# Sheet1.net
KiCad netlist of a schematic drawn in Altium Designer
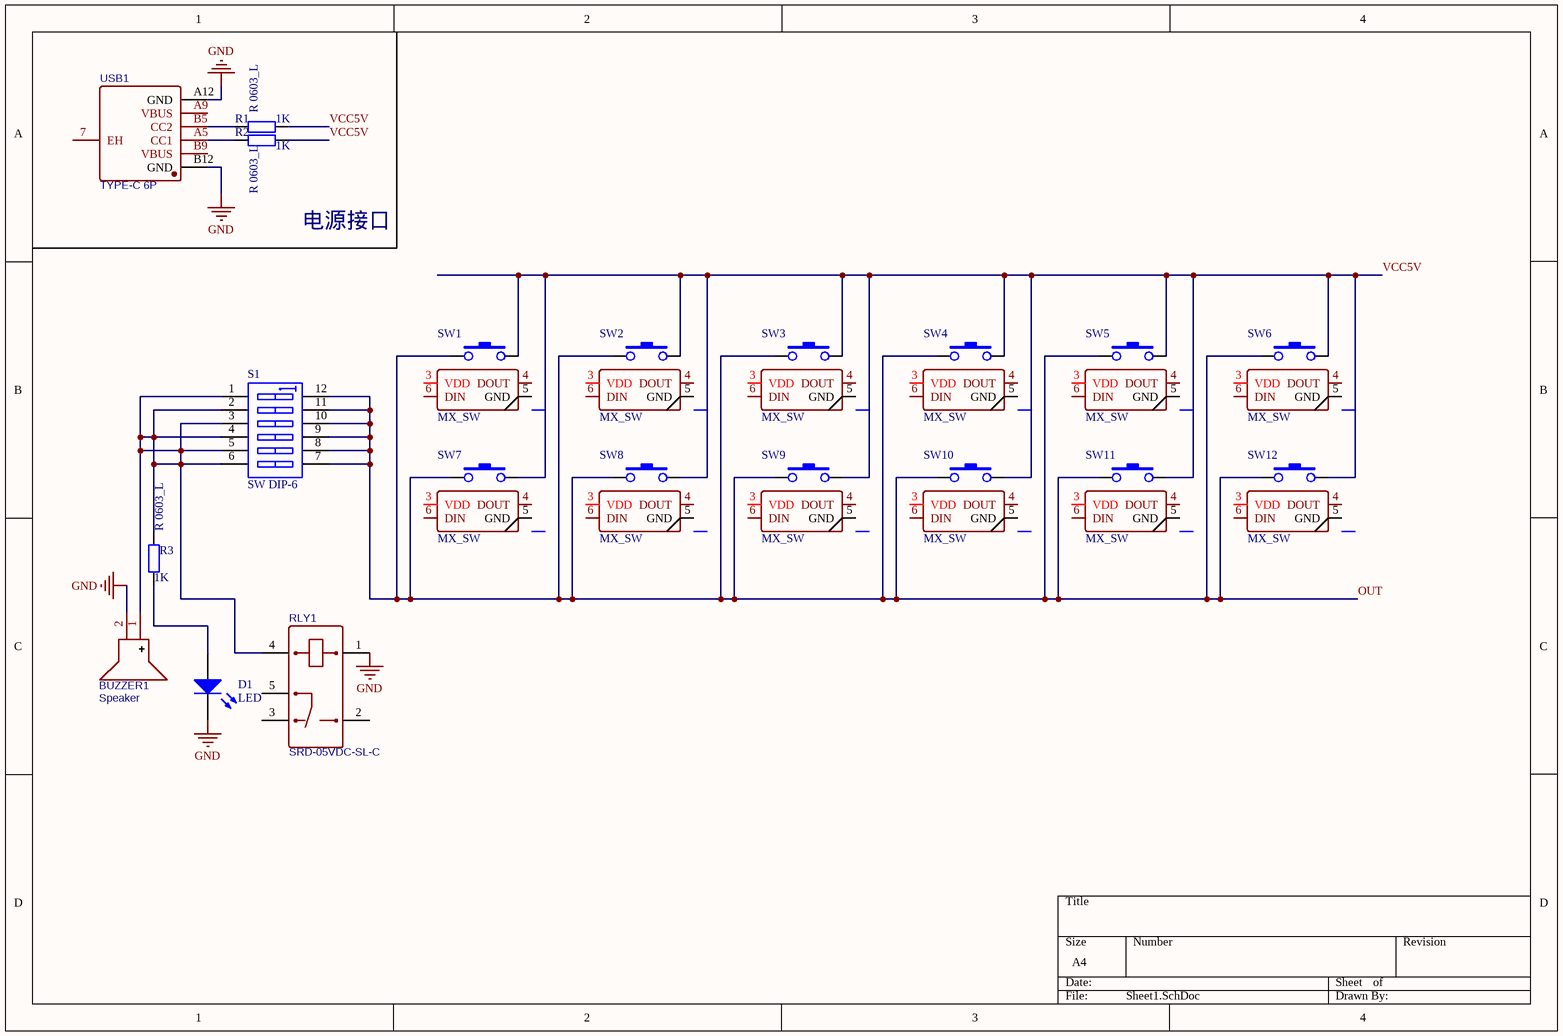
[diagram p0: Sheet1.SchDoc]

(export (version "E")
  (design (tool "Eeschema 10.0.6"))
  (components
    (comp (ref "BUZZER1")
      (value "Speaker")
      (footprint "Speaker")
      (fields
        (field (name "BOM_SUPPLIER PART") "C482357")
        (field (name "BOM_MANUFACTURER PART") "FMB1275-05")
        (field (name "CONTRIBUTOR") "LCSC")
      )
      (libsource (lib "Schlib1") (part "Speaker"))
    )
    (comp (ref "D1")
      (value "LED")
      (footprint "LED 0805R")
      (description "Typical INFRARED GaAs LED")
      (fields (field (name "PUBLISHER") "Altium Limited"))
      (libsource (lib "Schlib1") (part "LED 0805R 红"))
    )
    (comp (ref "R1")
      (value "R 0603_L")
      (footprint "R 0603_L")
      (description "Resistor")
      (fields (field (name "ALTIUM_VALUE") "1K") (field (name "PUBLISHER") "Altium Limited"))
      (libsource (lib "Schlib1") (part "R 0603_L"))
    )
    (comp (ref "R2")
      (value "R 0603_L")
      (footprint "R 0603_L")
      (description "Resistor")
      (fields (field (name "ALTIUM_VALUE") "1K") (field (name "PUBLISHER") "Altium Limited"))
      (libsource (lib "Schlib1") (part "R 0603_L"))
    )
    (comp (ref "R3")
      (value "R 0603_L")
      (footprint "R 0603_L")
      (description "Resistor")
      (fields (field (name "ALTIUM_VALUE") "1K") (field (name "PUBLISHER") "Altium Limited"))
      (libsource (lib "") (part "R 0603_L_1"))
    )
    (comp (ref "RLY1")
      (value "SRD-05VDC-SL-C")
      (footprint "SRD-05VDC-SL-C")
      (fields (field (name "BOM_SUPPLIER PART") "C35449"))
      (libsource (lib "Schlib1") (part "SRD-05VDC-SL-C"))
    )
    (comp (ref "S1")
      (value "SW DIP-6")
      (footprint "DIP-12/SW")
      (description "DIP Switch, 6 Position, SPST")
      (fields (field (name "PUBLISHER") "Altium Limited"))
      (libsource (lib "Miscellaneous Devices") (part "SW DIP-6"))
    )
    (comp (ref "SW1") (value "MX_SW") (footprint "MX_SW-1") (libsource (lib "Schlib1") (part "MX_SW-1")))
    (comp (ref "SW2") (value "MX_SW") (footprint "MX_SW-1") (libsource (lib "Schlib1") (part "MX_SW-1")))
    (comp (ref "SW3") (value "MX_SW") (footprint "MX_SW-1") (libsource (lib "Schlib1") (part "MX_SW-1")))
    (comp (ref "SW4") (value "MX_SW") (footprint "MX_SW-1") (libsource (lib "Schlib1") (part "MX_SW-1")))
    (comp (ref "SW5") (value "MX_SW") (footprint "MX_SW-1") (libsource (lib "Schlib1") (part "MX_SW-1")))
    (comp (ref "SW6") (value "MX_SW") (footprint "MX_SW-1") (libsource (lib "Schlib1") (part "MX_SW-1")))
    (comp (ref "SW7") (value "MX_SW") (footprint "MX_SW-1") (libsource (lib "Schlib1") (part "MX_SW-1")))
    (comp (ref "SW8") (value "MX_SW") (footprint "MX_SW-1") (libsource (lib "Schlib1") (part "MX_SW-1")))
    (comp (ref "SW9") (value "MX_SW") (footprint "MX_SW-1") (libsource (lib "Schlib1") (part "MX_SW-1")))
    (comp (ref "SW10") (value "MX_SW") (footprint "MX_SW-1") (libsource (lib "Schlib1") (part "MX_SW-1")))
    (comp (ref "SW11") (value "MX_SW") (footprint "MX_SW-1") (libsource (lib "Schlib1") (part "MX_SW-1")))
    (comp (ref "SW12") (value "MX_SW") (footprint "MX_SW-1") (libsource (lib "Schlib1") (part "MX_SW-1")))
    (comp (ref "USB1")
      (value "TYPE-C 6P")
      (footprint "TYPE-C-SMD_TYPE-C-6P")
      (fields (field (name "BOM_SUPPLIER PART") "C456012") (field (name "CONTRIBUTOR") "LCSC"))
      (libsource (lib "Schlib1") (part "TYPE-C 6P"))
    )
  )
  (nets
    (net (code "1") (name "/OUT") (class "Default")
      (node (ref "S1") (pin "10") (pinfunction "B3_10") (pintype "passive"))
      (node (ref "S1") (pin "11") (pinfunction "B2_11") (pintype "passive"))
      (node (ref "S1") (pin "12") (pinfunction "B1_12") (pintype "passive"))
      (node (ref "S1") (pin "7") (pinfunction "B6_7") (pintype "passive"))
      (node (ref "S1") (pin "8") (pinfunction "B5_8") (pintype "passive"))
      (node (ref "S1") (pin "9") (pinfunction "B4_9") (pintype "passive"))
      (node (ref "SW1") (pin "1") (pinfunction "1_1") (pintype "passive"))
      (node (ref "SW10") (pin "1") (pinfunction "1_1") (pintype "passive"))
      (node (ref "SW11") (pin "1") (pinfunction "1_1") (pintype "passive"))
      (node (ref "SW12") (pin "1") (pinfunction "1_1") (pintype "passive"))
      (node (ref "SW2") (pin "1") (pinfunction "1_1") (pintype "passive"))
      (node (ref "SW3") (pin "1") (pinfunction "1_1") (pintype "passive"))
      (node (ref "SW4") (pin "1") (pinfunction "1_1") (pintype "passive"))
      (node (ref "SW5") (pin "1") (pinfunction "1_1") (pintype "passive"))
      (node (ref "SW6") (pin "1") (pinfunction "1_1") (pintype "passive"))
      (node (ref "SW7") (pin "1") (pinfunction "1_1") (pintype "passive"))
      (node (ref "SW8") (pin "1") (pinfunction "1_1") (pintype "passive"))
      (node (ref "SW9") (pin "1") (pinfunction "1_1") (pintype "passive"))
    )
    (net (code "2") (name "/VCC5V") (class "Default")
      (node (ref "R1") (pin "2") (pinfunction "2_2") (pintype "passive"))
      (node (ref "R2") (pin "2") (pinfunction "2_2") (pintype "passive"))
      (node (ref "SW1") (pin "2") (pinfunction "2_2") (pintype "passive"))
      (node (ref "SW10") (pin "2") (pinfunction "2_2") (pintype "passive"))
      (node (ref "SW11") (pin "2") (pinfunction "2_2") (pintype "passive"))
      (node (ref "SW12") (pin "2") (pinfunction "2_2") (pintype "passive"))
      (node (ref "SW2") (pin "2") (pinfunction "2_2") (pintype "passive"))
      (node (ref "SW3") (pin "2") (pinfunction "2_2") (pintype "passive"))
      (node (ref "SW4") (pin "2") (pinfunction "2_2") (pintype "passive"))
      (node (ref "SW5") (pin "2") (pinfunction "2_2") (pintype "passive"))
      (node (ref "SW6") (pin "2") (pinfunction "2_2") (pintype "passive"))
      (node (ref "SW7") (pin "2") (pinfunction "2_2") (pintype "passive"))
      (node (ref "SW8") (pin "2") (pinfunction "2_2") (pintype "passive"))
      (node (ref "SW9") (pin "2") (pinfunction "2_2") (pintype "passive"))
    )
    (net (code "3") (name "GND") (class "Default")
      (node (ref "BUZZER1") (pin "2") (pinfunction "-_2") (pintype "passive"))
      (node (ref "D1") (pin "2") (pinfunction "K_2") (pintype "passive"))
      (node (ref "RLY1") (pin "1") (pinfunction "1_1") (pintype "passive"))
      (node (ref "USB1") (pin "A12") (pinfunction "GND_A12") (pintype "passive"))
      (node (ref "USB1") (pin "B12") (pinfunction "GND_B12") (pintype "passive"))
    )
    (net (code "4") (name "Net-(BUZZER1-+)") (class "Default")
      (node (ref "BUZZER1") (pin "1") (pinfunction "+_1") (pintype "passive"))
      (node (ref "R3") (pin "1") (pinfunction "1_1") (pintype "passive"))
      (node (ref "RLY1") (pin "4") (pinfunction "4_4") (pintype "passive"))
      (node (ref "S1") (pin "1") (pinfunction "A1_1") (pintype "passive"))
      (node (ref "S1") (pin "2") (pinfunction "A2_2") (pintype "passive"))
      (node (ref "S1") (pin "3") (pinfunction "A3_3") (pintype "passive"))
      (node (ref "S1") (pin "4") (pinfunction "A4_4") (pintype "passive"))
      (node (ref "S1") (pin "5") (pinfunction "A5_5") (pintype "passive"))
      (node (ref "S1") (pin "6") (pinfunction "A6_6") (pintype "passive"))
    )
    (net (code "5") (name "Net-(D1-A)") (class "Default")
      (node (ref "D1") (pin "1") (pinfunction "A_1") (pintype "passive"))
      (node (ref "R3") (pin "2") (pinfunction "2_2") (pintype "passive"))
    )
    (net (code "6") (name "Net-(USB1-CC1)") (class "Default")
      (node (ref "R2") (pin "1") (pinfunction "1_1") (pintype "passive"))
      (node (ref "USB1") (pin "A5") (pinfunction "CC1_A5") (pintype "passive"))
    )
    (net (code "7") (name "Net-(USB1-CC2)") (class "Default")
      (node (ref "R1") (pin "1") (pinfunction "1_1") (pintype "passive"))
      (node (ref "USB1") (pin "B5") (pinfunction "CC2_B5") (pintype "passive"))
    )
    (net (code "8") (name "unconnected-(RLY1-Pad2)") (class "Default")
      (node (ref "RLY1") (pin "2") (pinfunction "2_2") (pintype "passive"))
    )
    (net (code "9") (name "unconnected-(RLY1-Pad3)") (class "Default")
      (node (ref "RLY1") (pin "3") (pinfunction "3_3") (pintype "passive"))
    )
    (net (code "10") (name "unconnected-(RLY1-Pad5)") (class "Default")
      (node (ref "RLY1") (pin "5") (pinfunction "5_5") (pintype "passive"))
    )
    (net (code "11") (name "unconnected-(SW1-DIN-Pad6)") (class "Default")
      (node (ref "SW1") (pin "6") (pinfunction "DIN_6") (pintype "passive"))
    )
    (net (code "12") (name "unconnected-(SW1-DOUT-Pad4)") (class "Default")
      (node (ref "SW1") (pin "4") (pinfunction "DOUT_4") (pintype "passive"))
    )
    (net (code "13") (name "unconnected-(SW1-GND-Pad5)") (class "Default")
      (node (ref "SW1") (pin "5") (pinfunction "GND_5") (pintype "passive"))
    )
    (net (code "14") (name "unconnected-(SW1-VDD-Pad3)") (class "Default")
      (node (ref "SW1") (pin "3") (pinfunction "VDD_3") (pintype "passive"))
    )
    (net (code "15") (name "unconnected-(SW2-DIN-Pad6)") (class "Default")
      (node (ref "SW2") (pin "6") (pinfunction "DIN_6") (pintype "passive"))
    )
    (net (code "16") (name "unconnected-(SW2-DOUT-Pad4)") (class "Default")
      (node (ref "SW2") (pin "4") (pinfunction "DOUT_4") (pintype "passive"))
    )
    (net (code "17") (name "unconnected-(SW2-GND-Pad5)") (class "Default")
      (node (ref "SW2") (pin "5") (pinfunction "GND_5") (pintype "passive"))
    )
    (net (code "18") (name "unconnected-(SW2-VDD-Pad3)") (class "Default")
      (node (ref "SW2") (pin "3") (pinfunction "VDD_3") (pintype "passive"))
    )
    (net (code "19") (name "unconnected-(SW3-DIN-Pad6)") (class "Default")
      (node (ref "SW3") (pin "6") (pinfunction "DIN_6") (pintype "passive"))
    )
    (net (code "20") (name "unconnected-(SW3-DOUT-Pad4)") (class "Default")
      (node (ref "SW3") (pin "4") (pinfunction "DOUT_4") (pintype "passive"))
    )
    (net (code "21") (name "unconnected-(SW3-GND-Pad5)") (class "Default")
      (node (ref "SW3") (pin "5") (pinfunction "GND_5") (pintype "passive"))
    )
    (net (code "22") (name "unconnected-(SW3-VDD-Pad3)") (class "Default")
      (node (ref "SW3") (pin "3") (pinfunction "VDD_3") (pintype "passive"))
    )
    (net (code "23") (name "unconnected-(SW4-DIN-Pad6)") (class "Default")
      (node (ref "SW4") (pin "6") (pinfunction "DIN_6") (pintype "passive"))
    )
    (net (code "24") (name "unconnected-(SW4-DOUT-Pad4)") (class "Default")
      (node (ref "SW4") (pin "4") (pinfunction "DOUT_4") (pintype "passive"))
    )
    (net (code "25") (name "unconnected-(SW4-GND-Pad5)") (class "Default")
      (node (ref "SW4") (pin "5") (pinfunction "GND_5") (pintype "passive"))
    )
    (net (code "26") (name "unconnected-(SW4-VDD-Pad3)") (class "Default")
      (node (ref "SW4") (pin "3") (pinfunction "VDD_3") (pintype "passive"))
    )
    (net (code "27") (name "unconnected-(SW5-DIN-Pad6)") (class "Default")
      (node (ref "SW5") (pin "6") (pinfunction "DIN_6") (pintype "passive"))
    )
    (net (code "28") (name "unconnected-(SW5-DOUT-Pad4)") (class "Default")
      (node (ref "SW5") (pin "4") (pinfunction "DOUT_4") (pintype "passive"))
    )
    (net (code "29") (name "unconnected-(SW5-GND-Pad5)") (class "Default")
      (node (ref "SW5") (pin "5") (pinfunction "GND_5") (pintype "passive"))
    )
    (net (code "30") (name "unconnected-(SW5-VDD-Pad3)") (class "Default")
      (node (ref "SW5") (pin "3") (pinfunction "VDD_3") (pintype "passive"))
    )
    (net (code "31") (name "unconnected-(SW6-DIN-Pad6)") (class "Default")
      (node (ref "SW6") (pin "6") (pinfunction "DIN_6") (pintype "passive"))
    )
    (net (code "32") (name "unconnected-(SW6-DOUT-Pad4)") (class "Default")
      (node (ref "SW6") (pin "4") (pinfunction "DOUT_4") (pintype "passive"))
    )
    (net (code "33") (name "unconnected-(SW6-GND-Pad5)") (class "Default")
      (node (ref "SW6") (pin "5") (pinfunction "GND_5") (pintype "passive"))
    )
    (net (code "34") (name "unconnected-(SW6-VDD-Pad3)") (class "Default")
      (node (ref "SW6") (pin "3") (pinfunction "VDD_3") (pintype "passive"))
    )
    (net (code "35") (name "unconnected-(SW7-DIN-Pad6)") (class "Default")
      (node (ref "SW7") (pin "6") (pinfunction "DIN_6") (pintype "passive"))
    )
    (net (code "36") (name "unconnected-(SW7-DOUT-Pad4)") (class "Default")
      (node (ref "SW7") (pin "4") (pinfunction "DOUT_4") (pintype "passive"))
    )
    (net (code "37") (name "unconnected-(SW7-GND-Pad5)") (class "Default")
      (node (ref "SW7") (pin "5") (pinfunction "GND_5") (pintype "passive"))
    )
    (net (code "38") (name "unconnected-(SW7-VDD-Pad3)") (class "Default")
      (node (ref "SW7") (pin "3") (pinfunction "VDD_3") (pintype "passive"))
    )
    (net (code "39") (name "unconnected-(SW8-DIN-Pad6)") (class "Default")
      (node (ref "SW8") (pin "6") (pinfunction "DIN_6") (pintype "passive"))
    )
    (net (code "40") (name "unconnected-(SW8-DOUT-Pad4)") (class "Default")
      (node (ref "SW8") (pin "4") (pinfunction "DOUT_4") (pintype "passive"))
    )
    (net (code "41") (name "unconnected-(SW8-GND-Pad5)") (class "Default")
      (node (ref "SW8") (pin "5") (pinfunction "GND_5") (pintype "passive"))
    )
    (net (code "42") (name "unconnected-(SW8-VDD-Pad3)") (class "Default")
      (node (ref "SW8") (pin "3") (pinfunction "VDD_3") (pintype "passive"))
    )
    (net (code "43") (name "unconnected-(SW9-DIN-Pad6)") (class "Default")
      (node (ref "SW9") (pin "6") (pinfunction "DIN_6") (pintype "passive"))
    )
    (net (code "44") (name "unconnected-(SW9-DOUT-Pad4)") (class "Default")
      (node (ref "SW9") (pin "4") (pinfunction "DOUT_4") (pintype "passive"))
    )
    (net (code "45") (name "unconnected-(SW9-GND-Pad5)") (class "Default")
      (node (ref "SW9") (pin "5") (pinfunction "GND_5") (pintype "passive"))
    )
    (net (code "46") (name "unconnected-(SW9-VDD-Pad3)") (class "Default")
      (node (ref "SW9") (pin "3") (pinfunction "VDD_3") (pintype "passive"))
    )
    (net (code "47") (name "unconnected-(SW10-DIN-Pad6)") (class "Default")
      (node (ref "SW10") (pin "6") (pinfunction "DIN_6") (pintype "passive"))
    )
    (net (code "48") (name "unconnected-(SW10-DOUT-Pad4)") (class "Default")
      (node (ref "SW10") (pin "4") (pinfunction "DOUT_4") (pintype "passive"))
    )
    (net (code "49") (name "unconnected-(SW10-GND-Pad5)") (class "Default")
      (node (ref "SW10") (pin "5") (pinfunction "GND_5") (pintype "passive"))
    )
    (net (code "50") (name "unconnected-(SW10-VDD-Pad3)") (class "Default")
      (node (ref "SW10") (pin "3") (pinfunction "VDD_3") (pintype "passive"))
    )
    (net (code "51") (name "unconnected-(SW11-DIN-Pad6)") (class "Default")
      (node (ref "SW11") (pin "6") (pinfunction "DIN_6") (pintype "passive"))
    )
    (net (code "52") (name "unconnected-(SW11-DOUT-Pad4)") (class "Default")
      (node (ref "SW11") (pin "4") (pinfunction "DOUT_4") (pintype "passive"))
    )
    (net (code "53") (name "unconnected-(SW11-GND-Pad5)") (class "Default")
      (node (ref "SW11") (pin "5") (pinfunction "GND_5") (pintype "passive"))
    )
    (net (code "54") (name "unconnected-(SW11-VDD-Pad3)") (class "Default")
      (node (ref "SW11") (pin "3") (pinfunction "VDD_3") (pintype "passive"))
    )
    (net (code "55") (name "unconnected-(SW12-DIN-Pad6)") (class "Default")
      (node (ref "SW12") (pin "6") (pinfunction "DIN_6") (pintype "passive"))
    )
    (net (code "56") (name "unconnected-(SW12-DOUT-Pad4)") (class "Default")
      (node (ref "SW12") (pin "4") (pinfunction "DOUT_4") (pintype "passive"))
    )
    (net (code "57") (name "unconnected-(SW12-GND-Pad5)") (class "Default")
      (node (ref "SW12") (pin "5") (pinfunction "GND_5") (pintype "passive"))
    )
    (net (code "58") (name "unconnected-(SW12-VDD-Pad3)") (class "Default")
      (node (ref "SW12") (pin "3") (pinfunction "VDD_3") (pintype "passive"))
    )
    (net (code "59") (name "unconnected-(USB1-EH-Pad7)") (class "Default")
      (node (ref "USB1") (pin "7") (pinfunction "EH_7") (pintype "passive"))
    )
    (net (code "60") (name "unconnected-(USB1-VBUS-PadA9)") (class "Default")
      (node (ref "USB1") (pin "A9") (pinfunction "VBUS_A9") (pintype "passive"))
    )
    (net (code "61") (name "unconnected-(USB1-VBUS-PadB9)") (class "Default")
      (node (ref "USB1") (pin "B9") (pinfunction "VBUS_B9") (pintype "passive"))
    )
  )
)
